# BMP280-Breakout_v10.net
KiCad netlist of a schematic drawn in EAGLE
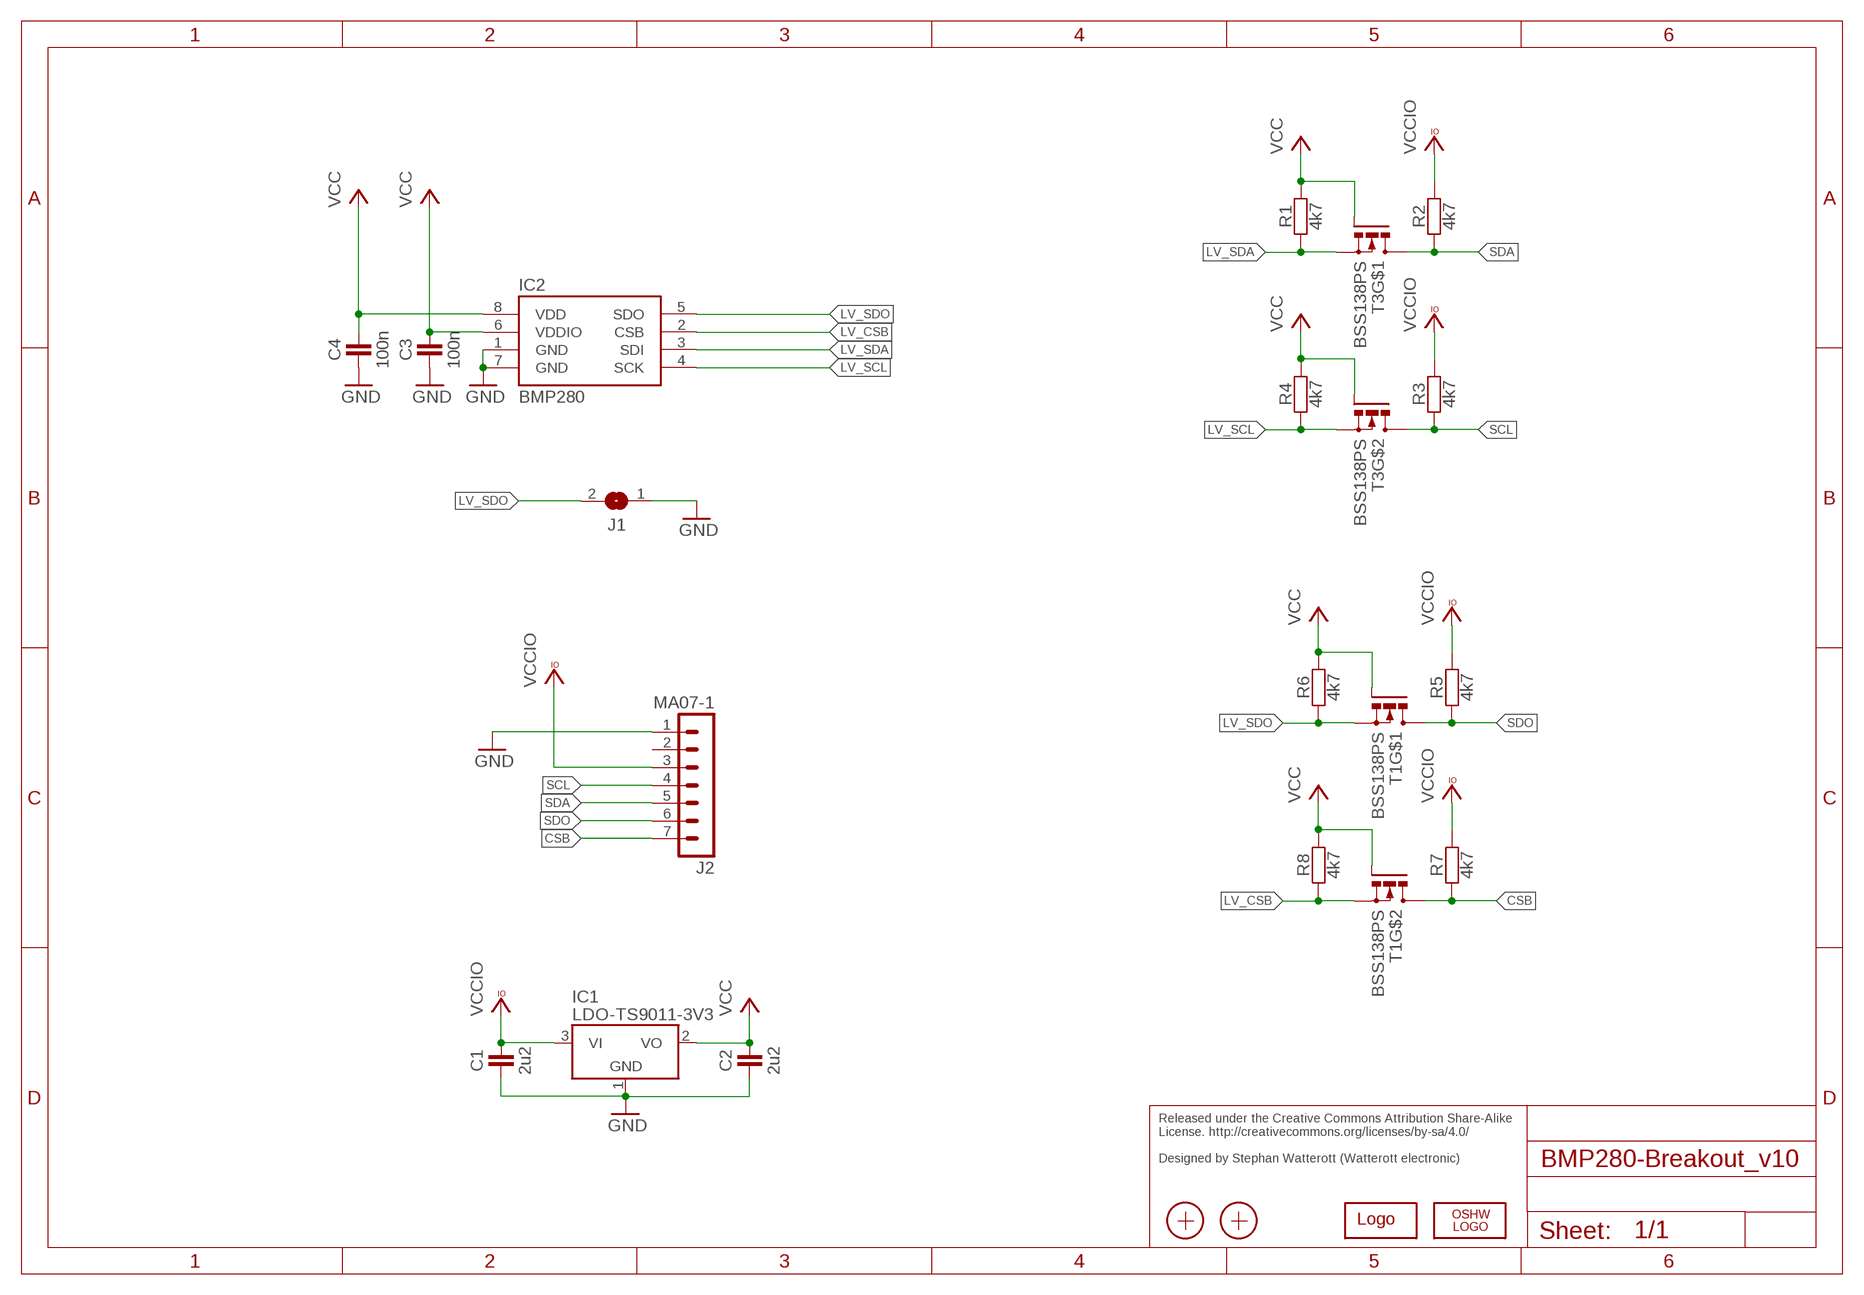
[diagram p0: schematic, sheet 1]

(export (version "E")
  (design (tool "Eeschema 10.0.6"))
  (components
    (comp (ref "C1")
      (value "2u2")
      (footprint "eagle-import:R0402")
      (libsource (lib "eagle-import") (part "CAPACITOR-C0402"))
    )
    (comp (ref "C2")
      (value "2u2")
      (footprint "eagle-import:R0402")
      (libsource (lib "eagle-import") (part "CAPACITOR-C0402"))
    )
    (comp (ref "C3")
      (value "100n")
      (footprint "eagle-import:R0402")
      (libsource (lib "eagle-import") (part "CAPACITOR-C0402"))
    )
    (comp (ref "C4")
      (value "100n")
      (footprint "eagle-import:R0402")
      (libsource (lib "eagle-import") (part "CAPACITOR-C0402"))
    )
    (comp (ref "IC1")
      (value "LDO-TS9011-3V3")
      (footprint "eagle-import:SOT23")
      (libsource (lib "eagle-import") (part "LDO-TS9011-3V3"))
    )
    (comp (ref "IC2")
      (value "BMP280")
      (footprint "eagle-import:LGA")
      (libsource (lib "eagle-import") (part "BMP280"))
    )
    (comp (ref "J1")
      (value "JUMPER2")
      (footprint "eagle-import:JUMPER2")
      (libsource (lib "eagle-import") (part "JUMPER2"))
    )
    (comp (ref "J2")
      (value "MA07-1")
      (footprint "eagle-import:MA07-1")
      (libsource (lib "eagle-import") (part "MA07-1"))
    )
    (comp (ref "LOGO1")
      (value "LOGO-S_PLACE_M")
      (footprint "eagle-import:SPARK_TPLACE_M")
      (libsource (lib "eagle-import") (part "LOGO-S_PLACE_M"))
    )
    (comp (ref "LOGO2")
      (value "OSHW_LOGOX0070")
      (footprint "eagle-import:OSHW_6X70")
      (libsource (lib "eagle-import") (part "OSHW_LOGOX0070"))
    )
    (comp (ref "R1")
      (value "4k7")
      (footprint "eagle-import:R0402")
      (libsource (lib "eagle-import") (part "RESISTOR-R0402"))
    )
    (comp (ref "R2")
      (value "4k7")
      (footprint "eagle-import:R0402")
      (libsource (lib "eagle-import") (part "RESISTOR-R0402"))
    )
    (comp (ref "R3")
      (value "4k7")
      (footprint "eagle-import:R0402")
      (libsource (lib "eagle-import") (part "RESISTOR-R0402"))
    )
    (comp (ref "R4")
      (value "4k7")
      (footprint "eagle-import:R0402")
      (libsource (lib "eagle-import") (part "RESISTOR-R0402"))
    )
    (comp (ref "R5")
      (value "4k7")
      (footprint "eagle-import:R0402")
      (libsource (lib "eagle-import") (part "RESISTOR-R0402"))
    )
    (comp (ref "R6")
      (value "4k7")
      (footprint "eagle-import:R0402")
      (libsource (lib "eagle-import") (part "RESISTOR-R0402"))
    )
    (comp (ref "R7")
      (value "4k7")
      (footprint "eagle-import:R0402")
      (libsource (lib "eagle-import") (part "RESISTOR-R0402"))
    )
    (comp (ref "R8")
      (value "4k7")
      (footprint "eagle-import:R0402")
      (libsource (lib "eagle-import") (part "RESISTOR-R0402"))
    )
    (comp (ref "T1")
      (value "BSS138PS")
      (footprint "eagle-import:SOT363")
      (libsource (lib "eagle-import") (part "BSS138PS"))
    )
    (comp (ref "T3")
      (value "BSS138PS")
      (footprint "eagle-import:SOT363")
      (libsource (lib "eagle-import") (part "BSS138PS"))
    )
    (comp (ref "X1")
      (value "PASSER-07")
      (footprint "eagle-import:PASSER_07MM")
      (libsource (lib "eagle-import") (part "PASSER-07"))
    )
    (comp (ref "X2")
      (value "PASSER-07")
      (footprint "eagle-import:PASSER_07MM")
      (libsource (lib "eagle-import") (part "PASSER-07"))
    )
  )
  (nets
    (net (code "1") (name "CSB") (class "Default")
      (node (ref "J2") (pin "7") (pinfunction "7_7") (pintype "passive"))
      (node (ref "R7") (pin "1") (pinfunction "1_1") (pintype "passive"))
      (node (ref "T1") (pin "3") (pinfunction "D_3") (pintype "passive"))
    )
    (net (code "2") (name "GND") (class "Default")
      (node (ref "C1") (pin "1") (pinfunction "1_1") (pintype "passive"))
      (node (ref "C2") (pin "1") (pinfunction "1_1") (pintype "passive"))
      (node (ref "C3") (pin "1") (pinfunction "1_1") (pintype "passive"))
      (node (ref "C4") (pin "1") (pinfunction "1_1") (pintype "passive"))
      (node (ref "IC1") (pin "1") (pinfunction "GND_1") (pintype "passive"))
      (node (ref "IC2") (pin "1") (pinfunction "GND_1") (pintype "power_in"))
      (node (ref "IC2") (pin "7") (pinfunction "GND_7") (pintype "power_in"))
      (node (ref "J1") (pin "1") (pinfunction "1_1") (pintype "passive"))
      (node (ref "J2") (pin "1") (pinfunction "1_1") (pintype "passive"))
    )
    (net (code "3") (name "LV_CSB") (class "Default")
      (node (ref "IC2") (pin "2") (pinfunction "CSB_2") (pintype "input"))
      (node (ref "R8") (pin "1") (pinfunction "1_1") (pintype "passive"))
      (node (ref "T1") (pin "4") (pinfunction "S_4") (pintype "passive"))
    )
    (net (code "4") (name "LV_SCL") (class "Default")
      (node (ref "IC2") (pin "4") (pinfunction "SCK_4") (pintype "input"))
      (node (ref "R4") (pin "1") (pinfunction "1_1") (pintype "passive"))
      (node (ref "T3") (pin "4") (pinfunction "S_4") (pintype "passive"))
    )
    (net (code "5") (name "LV_SDA") (class "Default")
      (node (ref "IC2") (pin "3") (pinfunction "SDI_3") (pintype "bidirectional"))
      (node (ref "R1") (pin "1") (pinfunction "1_1") (pintype "passive"))
      (node (ref "T3") (pin "1") (pinfunction "S_1") (pintype "passive"))
    )
    (net (code "6") (name "LV_SDO") (class "Default")
      (node (ref "IC2") (pin "5") (pinfunction "SDO_5") (pintype "bidirectional"))
      (node (ref "J1") (pin "2") (pinfunction "2_2") (pintype "passive"))
      (node (ref "R6") (pin "1") (pinfunction "1_1") (pintype "passive"))
      (node (ref "T1") (pin "1") (pinfunction "S_1") (pintype "passive"))
    )
    (net (code "7") (name "SCL") (class "Default")
      (node (ref "J2") (pin "4") (pinfunction "4_4") (pintype "passive"))
      (node (ref "R3") (pin "1") (pinfunction "1_1") (pintype "passive"))
      (node (ref "T3") (pin "3") (pinfunction "D_3") (pintype "passive"))
    )
    (net (code "8") (name "SDA") (class "Default")
      (node (ref "J2") (pin "5") (pinfunction "5_5") (pintype "passive"))
      (node (ref "R2") (pin "1") (pinfunction "1_1") (pintype "passive"))
      (node (ref "T3") (pin "6") (pinfunction "D_6") (pintype "passive"))
    )
    (net (code "9") (name "SDO") (class "Default")
      (node (ref "J2") (pin "6") (pinfunction "6_6") (pintype "passive"))
      (node (ref "R5") (pin "1") (pinfunction "1_1") (pintype "passive"))
      (node (ref "T1") (pin "6") (pinfunction "D_6") (pintype "passive"))
    )
    (net (code "10") (name "VCC") (class "Default")
      (node (ref "C2") (pin "2") (pinfunction "2_2") (pintype "passive"))
      (node (ref "C3") (pin "2") (pinfunction "2_2") (pintype "passive"))
      (node (ref "C4") (pin "2") (pinfunction "2_2") (pintype "passive"))
      (node (ref "IC1") (pin "2") (pinfunction "VO_2") (pintype "passive"))
      (node (ref "IC2") (pin "6") (pinfunction "VDDIO_6") (pintype "input"))
      (node (ref "IC2") (pin "8") (pinfunction "VDD_8") (pintype "power_in"))
      (node (ref "R1") (pin "2") (pinfunction "2_2") (pintype "passive"))
      (node (ref "R4") (pin "2") (pinfunction "2_2") (pintype "passive"))
      (node (ref "R6") (pin "2") (pinfunction "2_2") (pintype "passive"))
      (node (ref "R8") (pin "2") (pinfunction "2_2") (pintype "passive"))
      (node (ref "T1") (pin "2") (pinfunction "G_2") (pintype "passive"))
      (node (ref "T1") (pin "5") (pinfunction "G_5") (pintype "passive"))
      (node (ref "T3") (pin "2") (pinfunction "G_2") (pintype "passive"))
      (node (ref "T3") (pin "5") (pinfunction "G_5") (pintype "passive"))
    )
    (net (code "11") (name "VCCIO") (class "Default")
      (node (ref "C1") (pin "2") (pinfunction "2_2") (pintype "passive"))
      (node (ref "IC1") (pin "3") (pinfunction "VI_3") (pintype "input"))
      (node (ref "J2") (pin "3") (pinfunction "3_3") (pintype "passive"))
      (node (ref "R2") (pin "2") (pinfunction "2_2") (pintype "passive"))
      (node (ref "R3") (pin "2") (pinfunction "2_2") (pintype "passive"))
      (node (ref "R5") (pin "2") (pinfunction "2_2") (pintype "passive"))
      (node (ref "R7") (pin "2") (pinfunction "2_2") (pintype "passive"))
    )
    (net (code "12") (name "unconnected-(J2-Pad2)") (class "Default")
      (node (ref "J2") (pin "2") (pinfunction "2_2") (pintype "passive"))
    )
  )
)
